# 2_sensors.net
KiCad netlist of a schematic drawn in Altium Designer
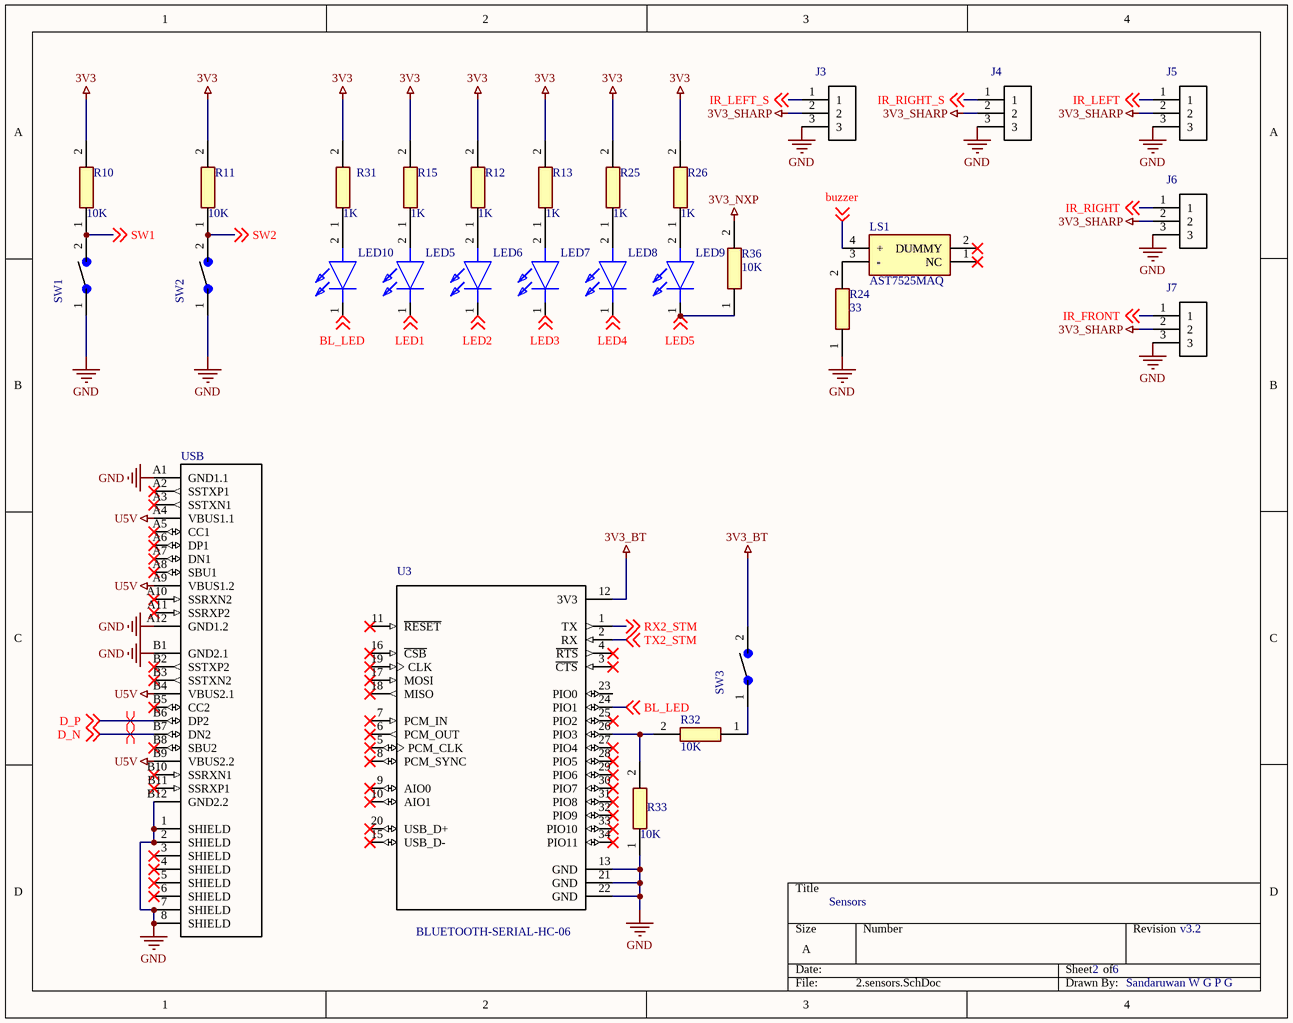
[diagram p0: 2.sensors.SchDoc]

(export (version "E")
  (design (tool "Eeschema 10.0.6"))
  (components
    (comp (ref "J3")
      (value "0022057035_5268-03A")
      (footprint "*MOLEX_0022057035_5268-03A")
      (description "Socket; wire-board; male; PIN: 3; 2.5mm; THT; SPOX; 3A; tinned; 20")
      (fields (field (name "MP") "0022057035 5268-03A") (field (name "MF") "Molex"))
      (libsource (lib "micromouse library") (part "0022057035_5268-03A"))
    )
    (comp (ref "J4")
      (value "0022057035_5268-03A")
      (footprint "*MOLEX_0022057035_5268-03A")
      (description "Socket; wire-board; male; PIN: 3; 2.5mm; THT; SPOX; 3A; tinned; 20")
      (fields (field (name "MP") "0022057035 5268-03A") (field (name "MF") "Molex"))
      (libsource (lib "micromouse library") (part "0022057035_5268-03A"))
    )
    (comp (ref "J5")
      (value "0022057035_5268-03A")
      (footprint "*MOLEX_0022057035_5268-03A")
      (description "Socket; wire-board; male; PIN: 3; 2.5mm; THT; SPOX; 3A; tinned; 20")
      (fields (field (name "MP") "0022057035 5268-03A") (field (name "MF") "Molex"))
      (libsource (lib "micromouse library") (part "0022057035_5268-03A"))
    )
    (comp (ref "J6")
      (value "0022057035_5268-03A")
      (footprint "*MOLEX_0022057035_5268-03A")
      (description "Socket; wire-board; male; PIN: 3; 2.5mm; THT; SPOX; 3A; tinned; 20")
      (fields (field (name "MP") "0022057035 5268-03A") (field (name "MF") "Molex"))
      (libsource (lib "micromouse library") (part "0022057035_5268-03A"))
    )
    (comp (ref "J7")
      (value "0022057035_5268-03A")
      (footprint "*MOLEX_0022057035_5268-03A")
      (description "Socket; wire-board; male; PIN: 3; 2.5mm; THT; SPOX; 3A; tinned; 20")
      (fields (field (name "MP") "0022057035 5268-03A") (field (name "MF") "Molex"))
      (libsource (lib "micromouse library") (part "0022057035_5268-03A"))
    )
    (comp (ref "LED5")
      (value "150080BS75000")
      (footprint "LEDC2012X80N")
      (description "LED")
      (fields
        (field (name "MOUSER PART NUMBER") "710-150080BS75000")
        (field (name "RS PART NUMBER") "8154228P")
      )
      (libsource (lib "micromouse library") (part "150080BS75000"))
    )
    (comp (ref "LED6")
      (value "150080BS75000")
      (footprint "LEDC2012X80N")
      (description "LED")
      (fields
        (field (name "MOUSER PART NUMBER") "710-150080BS75000")
        (field (name "RS PART NUMBER") "8154228P")
      )
      (libsource (lib "micromouse library") (part "150080BS75000"))
    )
    (comp (ref "LED7")
      (value "150080BS75000")
      (footprint "LEDC2012X80N")
      (description "LED")
      (fields
        (field (name "MOUSER PART NUMBER") "710-150080BS75000")
        (field (name "RS PART NUMBER") "8154228P")
      )
      (libsource (lib "micromouse library") (part "150080BS75000"))
    )
    (comp (ref "LED8")
      (value "150080BS75000")
      (footprint "LEDC2012X80N")
      (description "LED")
      (fields
        (field (name "MOUSER PART NUMBER") "710-150080BS75000")
        (field (name "RS PART NUMBER") "8154228P")
      )
      (libsource (lib "micromouse library") (part "150080BS75000"))
    )
    (comp (ref "LED9")
      (value "150080BS75000")
      (footprint "LEDC2012X80N")
      (description "LED")
      (fields
        (field (name "MOUSER PART NUMBER") "710-150080BS75000")
        (field (name "RS PART NUMBER") "8154228P")
      )
      (libsource (lib "micromouse library") (part "150080BS75000"))
    )
    (comp (ref "LED10")
      (value "150080BS75000")
      (footprint "LEDC2012X80N")
      (description "LED")
      (fields
        (field (name "MOUSER PART NUMBER") "710-150080BS75000")
        (field (name "RS PART NUMBER") "8154228P")
      )
      (libsource (lib "micromouse library") (part "150080BS75000"))
    )
    (comp (ref "LS1")
      (value "AST7525MAQ")
      (footprint "AST7525MAQ")
      (description "Loudspeaker or Buzzer")
      (fields (field (name "MOUSER PART NUMBER") "539-AST7525MAQ"))
      (libsource (lib "micromouse library") (part "AST7525MAQ"))
    )
    (comp (ref "R10")
      (value "10K")
      (footprint "RESC2012X65N")
      (description "Resistor")
      (fields
        (field (name "MANUFACTURER_PART_NUMBER") "CPF0805B100KE")
        (field (name "MOUSER PART NUMBER") "279-CPF0805B100KE")
      )
      (libsource (lib "micromouse library") (part "CPF0805B100KE"))
    )
    (comp (ref "R11")
      (value "10K")
      (footprint "RESC2012X65N")
      (description "Resistor")
      (fields
        (field (name "MANUFACTURER_PART_NUMBER") "CPF0805B100KE")
        (field (name "MOUSER PART NUMBER") "279-CPF0805B100KE")
      )
      (libsource (lib "micromouse library") (part "CPF0805B100KE"))
    )
    (comp (ref "R12")
      (value "1K")
      (footprint "RESC2012X65N")
      (description "Resistor")
      (fields
        (field (name "MANUFACTURER_PART_NUMBER") "CPF0805B100KE")
        (field (name "MOUSER PART NUMBER") "279-CPF0805B100KE")
      )
      (libsource (lib "micromouse library") (part "CPF0805B100KE"))
    )
    (comp (ref "R13")
      (value "1K")
      (footprint "RESC2012X65N")
      (description "Resistor")
      (fields
        (field (name "MANUFACTURER_PART_NUMBER") "CPF0805B100KE")
        (field (name "MOUSER PART NUMBER") "279-CPF0805B100KE")
      )
      (libsource (lib "micromouse library") (part "CPF0805B100KE"))
    )
    (comp (ref "R15")
      (value "1K")
      (footprint "RESC2012X65N")
      (description "Resistor")
      (fields
        (field (name "MANUFACTURER_PART_NUMBER") "CPF0805B100KE")
        (field (name "MOUSER PART NUMBER") "279-CPF0805B100KE")
      )
      (libsource (lib "micromouse library") (part "CPF0805B100KE"))
    )
    (comp (ref "R24")
      (value "33")
      (footprint "RESC1608X55N")
      (description "Resistor")
      (fields (field (name "Comment") "resistor"))
      (libsource (lib "micromouse library") (part "resistor"))
    )
    (comp (ref "R25")
      (value "1K")
      (footprint "RESC2012X65N")
      (description "Resistor")
      (fields
        (field (name "MANUFACTURER_PART_NUMBER") "CPF0805B100KE")
        (field (name "MOUSER PART NUMBER") "279-CPF0805B100KE")
      )
      (libsource (lib "micromouse library") (part "CPF0805B100KE"))
    )
    (comp (ref "R26")
      (value "1K")
      (footprint "RESC2012X65N")
      (description "Resistor")
      (fields
        (field (name "MANUFACTURER_PART_NUMBER") "CPF0805B100KE")
        (field (name "MOUSER PART NUMBER") "279-CPF0805B100KE")
      )
      (libsource (lib "micromouse library") (part "CPF0805B100KE"))
    )
    (comp (ref "R31")
      (value "1K")
      (footprint "RESC2012X65N")
      (description "Resistor")
      (fields
        (field (name "MANUFACTURER_PART_NUMBER") "CPF0805B100KE")
        (field (name "MOUSER PART NUMBER") "279-CPF0805B100KE")
      )
      (libsource (lib "micromouse library") (part "CPF0805"))
    )
    (comp (ref "R32")
      (value "10K")
      (footprint "RESC2012X65N")
      (description "Resistor")
      (fields
        (field (name "MANUFACTURER_PART_NUMBER") "CPF0805B100KE")
        (field (name "MOUSER PART NUMBER") "279-CPF0805B100KE")
      )
      (libsource (lib "") (part "CPF0805_1"))
    )
    (comp (ref "R33")
      (value "10K")
      (footprint "RESC2012X65N")
      (description "Resistor")
      (fields
        (field (name "MANUFACTURER_PART_NUMBER") "CPF0805B100KE")
        (field (name "MOUSER PART NUMBER") "279-CPF0805B100KE")
      )
      (libsource (lib "micromouse library") (part "CPF0805"))
    )
    (comp (ref "R36")
      (value "10K")
      (footprint "RESC1608X55N")
      (description "Resistor")
      (fields (field (name "Comment") "resistor"))
      (libsource (lib "micromouse library") (part "resistor"))
    )
    (comp (ref "SW1")
      (value "1437566-3")
      (footprint "*TE_FSMSM")
      (description "Switch Tactile OFF _ON_ SPST Rectangular Button Gull Wing 0.05A 12VDC SMD Loose Piece")
      (fields (field (name "MF") "TE Connectivity") (field (name "MP") "FSMSM"))
      (libsource (lib "micromouse library") (part "FSMSM"))
    )
    (comp (ref "SW2")
      (value "1437566-3")
      (footprint "*TE_FSMSM")
      (description "Switch Tactile OFF _ON_ SPST Rectangular Button Gull Wing 0.05A 12VDC SMD Loose Piece")
      (fields (field (name "MF") "TE Connectivity") (field (name "MP") "FSMSM"))
      (libsource (lib "micromouse library") (part "FSMSM"))
    )
    (comp (ref "SW3")
      (value "1437566-3")
      (footprint "*TE_FSMSM")
      (description "Switch Tactile OFF _ON_ SPST Rectangular Button Gull Wing 0.05A 12VDC SMD Loose Piece")
      (fields (field (name "MF") "TE Connectivity") (field (name "MP") "FSMSM"))
      (libsource (lib "micromouse library") (part "FSMSM"))
    )
    (comp (ref "U3")
      (value "BLUETOOTH-SERIAL-HC-06")
      (footprint "*XCVR_BLUETOOTH-SERIAL-HC-06")
      (description "Bluetooth Modules _802.15.1_ BLUETOOTH-SERIAL-HC-06")
      (fields (field (name "MF") "Olimex"))
      (libsource (lib "altium-import") (part "root_0_BLUETOOTH-SERIAL-HC-06_"))
    )
    (comp (ref "USB")
      (value "USB4070-XX-X_REVC")
      (footprint "*GCT_USB4070-XX-X_REVC_USB4070-XX-X_REVC(Primary)")
      (description "Usb Type c Rec. 30 , Vertical, Smt With Stakes & Pegs, Tray")
      (fields (field (name "MP") "USB4070-30-B") (field (name "MF") "Global Connector Technology"))
      (libsource (lib "micromouse library") (part "USB4070-XX-X_REVC"))
    )
  )
  (nets
    (net (code "1") (name "3V3") (class "Default")
      (node (ref "R10") (pin "2") (pinfunction "2_2") (pintype "passive"))
      (node (ref "R11") (pin "2") (pinfunction "2_2") (pintype "passive"))
      (node (ref "R12") (pin "2") (pinfunction "2_2") (pintype "passive"))
      (node (ref "R13") (pin "2") (pinfunction "2_2") (pintype "passive"))
      (node (ref "R15") (pin "2") (pinfunction "2_2") (pintype "passive"))
      (node (ref "R25") (pin "2") (pinfunction "2_2") (pintype "passive"))
      (node (ref "R26") (pin "2") (pinfunction "2_2") (pintype "passive"))
      (node (ref "R31") (pin "2") (pinfunction "2_2") (pintype "passive"))
    )
    (net (code "2") (name "3V3_BT") (class "Default")
      (node (ref "SW3") (pin "2") (pinfunction "2_2") (pintype "passive"))
      (node (ref "U3") (pin "12") (pinfunction "3V3_12") (pintype "power_in"))
    )
    (net (code "3") (name "3V3_NXP") (class "Default")
      (node (ref "R36") (pin "2") (pinfunction "2_2") (pintype "passive"))
    )
    (net (code "4") (name "3V3_SHARP") (class "Default")
      (node (ref "J3") (pin "2") (pinfunction "2_2") (pintype "passive"))
      (node (ref "J4") (pin "2") (pinfunction "2_2") (pintype "passive"))
      (node (ref "J5") (pin "2") (pinfunction "2_2") (pintype "passive"))
      (node (ref "J6") (pin "2") (pinfunction "2_2") (pintype "passive"))
      (node (ref "J7") (pin "2") (pinfunction "2_2") (pintype "passive"))
    )
    (net (code "5") (name "BL_LED") (class "Default")
      (node (ref "LED10") (pin "1") (pinfunction "K_1") (pintype "passive"))
      (node (ref "U3") (pin "24") (pinfunction "PIO1_24") (pintype "bidirectional"))
    )
    (net (code "6") (name "D_N") (class "Default")
      (node (ref "USB") (pin "B7") (pinfunction "DN2_B7") (pintype "bidirectional"))
    )
    (net (code "7") (name "D_P") (class "Default")
      (node (ref "USB") (pin "B6") (pinfunction "DP2_B6") (pintype "bidirectional"))
    )
    (net (code "8") (name "GND") (class "Default")
      (node (ref "J3") (pin "3") (pinfunction "3_3") (pintype "passive"))
      (node (ref "J4") (pin "3") (pinfunction "3_3") (pintype "passive"))
      (node (ref "J5") (pin "3") (pinfunction "3_3") (pintype "passive"))
      (node (ref "J6") (pin "3") (pinfunction "3_3") (pintype "passive"))
      (node (ref "J7") (pin "3") (pinfunction "3_3") (pintype "passive"))
      (node (ref "R24") (pin "1") (pinfunction "1_1") (pintype "passive"))
      (node (ref "R33") (pin "1") (pinfunction "1_1") (pintype "passive"))
      (node (ref "SW1") (pin "1") (pinfunction "1_1") (pintype "passive"))
      (node (ref "SW2") (pin "1") (pinfunction "1_1") (pintype "passive"))
      (node (ref "U3") (pin "13") (pinfunction "GND_13") (pintype "power_in"))
      (node (ref "U3") (pin "21") (pinfunction "GND_21") (pintype "power_in"))
      (node (ref "U3") (pin "22") (pinfunction "GND_22") (pintype "power_in"))
      (node (ref "USB") (pin "1") (pinfunction "SHIELD_1") (pintype "passive"))
      (node (ref "USB") (pin "2") (pinfunction "SHIELD_2") (pintype "passive"))
      (node (ref "USB") (pin "7") (pinfunction "SHIELD_7") (pintype "passive"))
      (node (ref "USB") (pin "8") (pinfunction "SHIELD_8") (pintype "passive"))
      (node (ref "USB") (pin "A1") (pinfunction "GND1.1_A1") (pintype "power_in"))
      (node (ref "USB") (pin "A12") (pinfunction "GND1.2_A12") (pintype "power_in"))
      (node (ref "USB") (pin "B1") (pinfunction "GND2.1_B1") (pintype "power_in"))
      (node (ref "USB") (pin "B12") (pinfunction "GND2.2_B12") (pintype "power_in"))
    )
    (net (code "9") (name "IR_FRONT") (class "Default")
      (node (ref "J7") (pin "1") (pinfunction "1_1") (pintype "passive"))
    )
    (net (code "10") (name "IR_LEFT") (class "Default")
      (node (ref "J5") (pin "1") (pinfunction "1_1") (pintype "passive"))
    )
    (net (code "11") (name "IR_LEFT_S") (class "Default")
      (node (ref "J3") (pin "1") (pinfunction "1_1") (pintype "passive"))
    )
    (net (code "12") (name "IR_RIGHT") (class "Default")
      (node (ref "J6") (pin "1") (pinfunction "1_1") (pintype "passive"))
    )
    (net (code "13") (name "IR_RIGHT_S") (class "Default")
      (node (ref "J4") (pin "1") (pinfunction "1_1") (pintype "passive"))
    )
    (net (code "14") (name "LED1") (class "Default")
      (node (ref "LED5") (pin "1") (pinfunction "K_1") (pintype "passive"))
    )
    (net (code "15") (name "LED2") (class "Default")
      (node (ref "LED6") (pin "1") (pinfunction "K_1") (pintype "passive"))
    )
    (net (code "16") (name "LED3") (class "Default")
      (node (ref "LED7") (pin "1") (pinfunction "K_1") (pintype "passive"))
    )
    (net (code "17") (name "LED4") (class "Default")
      (node (ref "LED8") (pin "1") (pinfunction "K_1") (pintype "passive"))
    )
    (net (code "18") (name "LED5") (class "Default")
      (node (ref "LED9") (pin "1") (pinfunction "K_1") (pintype "passive"))
      (node (ref "R36") (pin "1") (pinfunction "1_1") (pintype "passive"))
    )
    (net (code "19") (name "Net-(LED5-A)") (class "Default")
      (node (ref "LED5") (pin "2") (pinfunction "A_2") (pintype "passive"))
      (node (ref "R15") (pin "1") (pinfunction "1_1") (pintype "passive"))
    )
    (net (code "20") (name "Net-(LED6-A)") (class "Default")
      (node (ref "LED6") (pin "2") (pinfunction "A_2") (pintype "passive"))
      (node (ref "R12") (pin "1") (pinfunction "1_1") (pintype "passive"))
    )
    (net (code "21") (name "Net-(LED7-A)") (class "Default")
      (node (ref "LED7") (pin "2") (pinfunction "A_2") (pintype "passive"))
      (node (ref "R13") (pin "1") (pinfunction "1_1") (pintype "passive"))
    )
    (net (code "22") (name "Net-(LED8-A)") (class "Default")
      (node (ref "LED8") (pin "2") (pinfunction "A_2") (pintype "passive"))
      (node (ref "R25") (pin "1") (pinfunction "1_1") (pintype "passive"))
    )
    (net (code "23") (name "Net-(LED9-A)") (class "Default")
      (node (ref "LED9") (pin "2") (pinfunction "A_2") (pintype "passive"))
      (node (ref "R26") (pin "1") (pinfunction "1_1") (pintype "passive"))
    )
    (net (code "24") (name "Net-(LED10-A)") (class "Default")
      (node (ref "LED10") (pin "2") (pinfunction "A_2") (pintype "passive"))
      (node (ref "R31") (pin "1") (pinfunction "1_1") (pintype "passive"))
    )
    (net (code "25") (name "Net-(LS1--)") (class "Default")
      (node (ref "LS1") (pin "3") (pinfunction "-_3") (pintype "passive"))
      (node (ref "R24") (pin "2") (pinfunction "2_2") (pintype "passive"))
    )
    (net (code "26") (name "Net-(R32-Pad1)") (class "Default")
      (node (ref "R32") (pin "1") (pinfunction "1_1") (pintype "passive"))
      (node (ref "SW3") (pin "1") (pinfunction "1_1") (pintype "passive"))
    )
    (net (code "27") (name "Net-(U3-PIO3)") (class "Default")
      (node (ref "R32") (pin "2") (pinfunction "2_2") (pintype "passive"))
      (node (ref "R33") (pin "2") (pinfunction "2_2") (pintype "passive"))
      (node (ref "U3") (pin "26") (pinfunction "PIO3_26") (pintype "bidirectional"))
    )
    (net (code "28") (name "RX2_STM") (class "Default")
      (node (ref "U3") (pin "1") (pinfunction "TX_1") (pintype "output"))
    )
    (net (code "29") (name "SW1") (class "Default")
      (node (ref "R10") (pin "1") (pinfunction "1_1") (pintype "passive"))
      (node (ref "SW1") (pin "2") (pinfunction "2_2") (pintype "passive"))
    )
    (net (code "30") (name "SW2") (class "Default")
      (node (ref "R11") (pin "1") (pinfunction "1_1") (pintype "passive"))
      (node (ref "SW2") (pin "2") (pinfunction "2_2") (pintype "passive"))
    )
    (net (code "31") (name "TX2_STM") (class "Default")
      (node (ref "U3") (pin "2") (pinfunction "RX_2") (pintype "input"))
    )
    (net (code "32") (name "U5V") (class "Default")
      (node (ref "USB") (pin "A4") (pinfunction "VBUS1.1_A4") (pintype "power_in"))
      (node (ref "USB") (pin "A9") (pinfunction "VBUS1.2_A9") (pintype "power_in"))
      (node (ref "USB") (pin "B4") (pinfunction "VBUS2.1_B4") (pintype "power_in"))
      (node (ref "USB") (pin "B9") (pinfunction "VBUS2.2_B9") (pintype "power_in"))
    )
    (net (code "33") (name "buzzer") (class "Default")
      (node (ref "LS1") (pin "4") (pinfunction "+_4") (pintype "passive"))
    )
    (net (code "34") (name "unconnected-(LS1-DUMMY-Pad2)") (class "Default")
      (node (ref "LS1") (pin "2") (pinfunction "DUMMY_2") (pintype "passive+no_connect"))
    )
    (net (code "35") (name "unconnected-(LS1-NC-Pad1)") (class "Default")
      (node (ref "LS1") (pin "1") (pinfunction "NC_1") (pintype "passive+no_connect"))
    )
    (net (code "36") (name "unconnected-(U3-AIO0-Pad9)") (class "Default")
      (node (ref "U3") (pin "9") (pinfunction "AIO0_9") (pintype "bidirectional+no_connect"))
    )
    (net (code "37") (name "unconnected-(U3-AIO1-Pad10)") (class "Default")
      (node (ref "U3") (pin "10") (pinfunction "AIO1_10") (pintype "bidirectional+no_connect"))
    )
    (net (code "38") (name "unconnected-(U3-CLK-Pad19)") (class "Default")
      (node (ref "U3") (pin "19") (pinfunction "CLK_19") (pintype "input+no_connect"))
    )
    (net (code "39") (name "unconnected-(U3-MISO-Pad18)") (class "Default")
      (node (ref "U3") (pin "18") (pinfunction "MISO_18") (pintype "output+no_connect"))
    )
    (net (code "40") (name "unconnected-(U3-MOSI-Pad17)") (class "Default")
      (node (ref "U3") (pin "17") (pinfunction "MOSI_17") (pintype "input+no_connect"))
    )
    (net (code "41") (name "unconnected-(U3-PCM_CLK-Pad5)") (class "Default")
      (node (ref "U3") (pin "5") (pinfunction "PCM_CLK_5") (pintype "bidirectional+no_connect"))
    )
    (net (code "42") (name "unconnected-(U3-PCM_IN-Pad7)") (class "Default")
      (node (ref "U3") (pin "7") (pinfunction "PCM_IN_7") (pintype "input+no_connect"))
    )
    (net (code "43") (name "unconnected-(U3-PCM_OUT-Pad6)") (class "Default")
      (node (ref "U3") (pin "6") (pinfunction "PCM_OUT_6") (pintype "output+no_connect"))
    )
    (net (code "44") (name "unconnected-(U3-PCM_SYNC-Pad8)") (class "Default")
      (node (ref "U3") (pin "8") (pinfunction "PCM_SYNC_8") (pintype "bidirectional+no_connect"))
    )
    (net (code "45") (name "unconnected-(U3-PIO0-Pad23)") (class "Default")
      (node (ref "U3") (pin "23") (pinfunction "PIO0_23") (pintype "bidirectional"))
    )
    (net (code "46") (name "unconnected-(U3-PIO2-Pad25)") (class "Default")
      (node (ref "U3") (pin "25") (pinfunction "PIO2_25") (pintype "bidirectional+no_connect"))
    )
    (net (code "47") (name "unconnected-(U3-PIO4-Pad27)") (class "Default")
      (node (ref "U3") (pin "27") (pinfunction "PIO4_27") (pintype "bidirectional+no_connect"))
    )
    (net (code "48") (name "unconnected-(U3-PIO5-Pad28)") (class "Default")
      (node (ref "U3") (pin "28") (pinfunction "PIO5_28") (pintype "bidirectional+no_connect"))
    )
    (net (code "49") (name "unconnected-(U3-PIO6-Pad29)") (class "Default")
      (node (ref "U3") (pin "29") (pinfunction "PIO6_29") (pintype "bidirectional+no_connect"))
    )
    (net (code "50") (name "unconnected-(U3-PIO7-Pad30)") (class "Default")
      (node (ref "U3") (pin "30") (pinfunction "PIO7_30") (pintype "bidirectional+no_connect"))
    )
    (net (code "51") (name "unconnected-(U3-PIO8-Pad31)") (class "Default")
      (node (ref "U3") (pin "31") (pinfunction "PIO8_31") (pintype "bidirectional+no_connect"))
    )
    (net (code "52") (name "unconnected-(U3-PIO9-Pad32)") (class "Default")
      (node (ref "U3") (pin "32") (pinfunction "PIO9_32") (pintype "bidirectional+no_connect"))
    )
    (net (code "53") (name "unconnected-(U3-PIO10-Pad33)") (class "Default")
      (node (ref "U3") (pin "33") (pinfunction "PIO10_33") (pintype "bidirectional+no_connect"))
    )
    (net (code "54") (name "unconnected-(U3-PIO11-Pad34)") (class "Default")
      (node (ref "U3") (pin "34") (pinfunction "PIO11_34") (pintype "bidirectional+no_connect"))
    )
    (net (code "55") (name "unconnected-(U3-USB_D+-Pad20)") (class "Default")
      (node (ref "U3") (pin "20") (pinfunction "USB_D+_20") (pintype "bidirectional+no_connect"))
    )
    (net (code "56") (name "unconnected-(U3-USB_D--Pad15)") (class "Default")
      (node (ref "U3") (pin "15") (pinfunction "USB_D-_15") (pintype "bidirectional+no_connect"))
    )
    (net (code "57") (name "unconnected-(U3-~{CSB}-Pad16)") (class "Default")
      (node (ref "U3") (pin "16") (pinfunction "~{CSB}_16") (pintype "input+no_connect"))
    )
    (net (code "58") (name "unconnected-(U3-~{CTS}-Pad3)") (class "Default")
      (node (ref "U3") (pin "3") (pinfunction "~{CTS}_3") (pintype "input+no_connect"))
    )
    (net (code "59") (name "unconnected-(U3-~{RESET}-Pad11)") (class "Default")
      (node (ref "U3") (pin "11") (pinfunction "~{RESET}_11") (pintype "input+no_connect"))
    )
    (net (code "60") (name "unconnected-(U3-~{RTS}-Pad4)") (class "Default")
      (node (ref "U3") (pin "4") (pinfunction "~{RTS}_4") (pintype "output+no_connect"))
    )
    (net (code "61") (name "unconnected-(USB-CC1-PadA5)") (class "Default")
      (node (ref "USB") (pin "A5") (pinfunction "CC1_A5") (pintype "bidirectional+no_connect"))
    )
    (net (code "62") (name "unconnected-(USB-CC2-PadB5)") (class "Default")
      (node (ref "USB") (pin "B5") (pinfunction "CC2_B5") (pintype "bidirectional+no_connect"))
    )
    (net (code "63") (name "unconnected-(USB-DN1-PadA7)") (class "Default")
      (node (ref "USB") (pin "A7") (pinfunction "DN1_A7") (pintype "bidirectional+no_connect"))
    )
    (net (code "64") (name "unconnected-(USB-DP1-PadA6)") (class "Default")
      (node (ref "USB") (pin "A6") (pinfunction "DP1_A6") (pintype "bidirectional+no_connect"))
    )
    (net (code "65") (name "unconnected-(USB-SBU1-PadA8)") (class "Default")
      (node (ref "USB") (pin "A8") (pinfunction "SBU1_A8") (pintype "bidirectional+no_connect"))
    )
    (net (code "66") (name "unconnected-(USB-SBU2-PadB8)") (class "Default")
      (node (ref "USB") (pin "B8") (pinfunction "SBU2_B8") (pintype "bidirectional+no_connect"))
    )
    (net (code "67") (name "unconnected-(USB-SHIELD-Pad3)") (class "Default")
      (node (ref "USB") (pin "3") (pinfunction "SHIELD_3") (pintype "passive+no_connect"))
    )
    (net (code "68") (name "unconnected-(USB-SHIELD-Pad4)") (class "Default")
      (node (ref "USB") (pin "4") (pinfunction "SHIELD_4") (pintype "passive+no_connect"))
    )
    (net (code "69") (name "unconnected-(USB-SHIELD-Pad5)") (class "Default")
      (node (ref "USB") (pin "5") (pinfunction "SHIELD_5") (pintype "passive+no_connect"))
    )
    (net (code "70") (name "unconnected-(USB-SHIELD-Pad6)") (class "Default")
      (node (ref "USB") (pin "6") (pinfunction "SHIELD_6") (pintype "passive+no_connect"))
    )
    (net (code "71") (name "unconnected-(USB-SSRXN1-PadB10)") (class "Default")
      (node (ref "USB") (pin "B10") (pinfunction "SSRXN1_B10") (pintype "input+no_connect"))
    )
    (net (code "72") (name "unconnected-(USB-SSRXN2-PadA10)") (class "Default")
      (node (ref "USB") (pin "A10") (pinfunction "SSRXN2_A10") (pintype "input+no_connect"))
    )
    (net (code "73") (name "unconnected-(USB-SSRXP1-PadB11)") (class "Default")
      (node (ref "USB") (pin "B11") (pinfunction "SSRXP1_B11") (pintype "input+no_connect"))
    )
    (net (code "74") (name "unconnected-(USB-SSRXP2-PadA11)") (class "Default")
      (node (ref "USB") (pin "A11") (pinfunction "SSRXP2_A11") (pintype "input+no_connect"))
    )
    (net (code "75") (name "unconnected-(USB-SSTXN1-PadA3)") (class "Default")
      (node (ref "USB") (pin "A3") (pinfunction "SSTXN1_A3") (pintype "output+no_connect"))
    )
    (net (code "76") (name "unconnected-(USB-SSTXN2-PadB3)") (class "Default")
      (node (ref "USB") (pin "B3") (pinfunction "SSTXN2_B3") (pintype "output+no_connect"))
    )
    (net (code "77") (name "unconnected-(USB-SSTXP1-PadA2)") (class "Default")
      (node (ref "USB") (pin "A2") (pinfunction "SSTXP1_A2") (pintype "output+no_connect"))
    )
    (net (code "78") (name "unconnected-(USB-SSTXP2-PadB2)") (class "Default")
      (node (ref "USB") (pin "B2") (pinfunction "SSTXP2_B2") (pintype "output+no_connect"))
    )
  )
)
